# ElekShemaRelais.net
KiCad netlist of a schematic drawn in Altium Designer
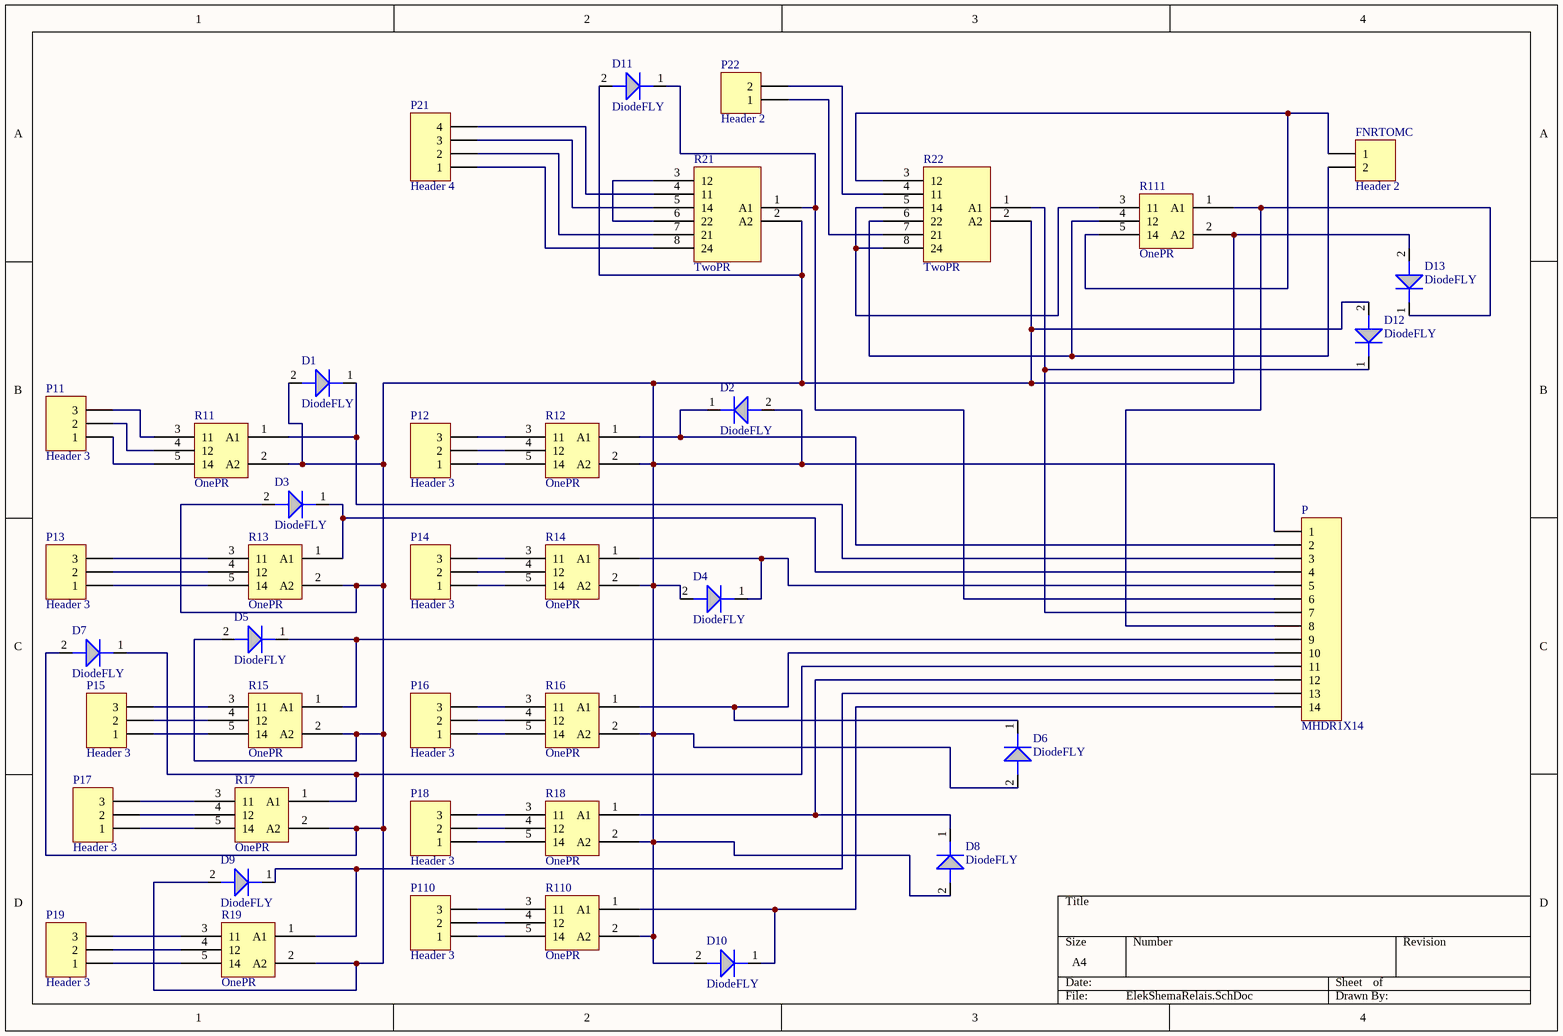
[diagram p0: ElekShemaRelais.SchDoc]

(export (version "E")
  (design (tool "Eeschema 10.0.6"))
  (components
    (comp (ref "D1") (value "DiodeFLY") (footprint "DiodeFLY") (libsource (lib "Schlib1") (part "DiodeFLY")))
    (comp (ref "D2") (value "DiodeFLY") (footprint "DiodeFLY") (libsource (lib "Schlib1") (part "DiodeFLY")))
    (comp (ref "D3") (value "DiodeFLY") (footprint "DiodeFLY") (libsource (lib "Schlib1") (part "DiodeFLY")))
    (comp (ref "D4") (value "DiodeFLY") (footprint "DiodeFLY") (libsource (lib "Schlib1") (part "DiodeFLY")))
    (comp (ref "D5") (value "DiodeFLY") (footprint "DiodeFLY") (libsource (lib "Schlib1") (part "DiodeFLY")))
    (comp (ref "D6") (value "DiodeFLY") (footprint "DiodeFLY") (libsource (lib "Schlib1") (part "DiodeFLY")))
    (comp (ref "D7") (value "DiodeFLY") (footprint "DiodeFLY") (libsource (lib "Schlib1") (part "DiodeFLY")))
    (comp (ref "D8") (value "DiodeFLY") (footprint "DiodeFLY") (libsource (lib "Schlib1") (part "DiodeFLY")))
    (comp (ref "D9") (value "DiodeFLY") (footprint "DiodeFLY") (libsource (lib "Schlib1") (part "DiodeFLY")))
    (comp (ref "D10") (value "DiodeFLY") (footprint "DiodeFLY") (libsource (lib "Schlib1") (part "DiodeFLY")))
    (comp (ref "D11") (value "DiodeFLY") (footprint "DiodeFLY") (libsource (lib "Schlib1") (part "DiodeFLY")))
    (comp (ref "D12") (value "DiodeFLY") (footprint "DiodeFLY") (libsource (lib "Schlib1") (part "DiodeFLY")))
    (comp (ref "D13") (value "DiodeFLY") (footprint "DiodeFLY") (libsource (lib "Schlib1") (part "DiodeFLY")))
    (comp (ref "FNRTOMC")
      (value "Header 2")
      (footprint "HDR2")
      (description "Header, 2-Pin")
      (fields (field (name "PUBLISHER") "Altium Limited"))
      (libsource (lib "") (part "Header 2_1"))
    )
    (comp (ref "P")
      (value "MHDR1X14")
      (footprint "HDR14")
      (description "Header, 14-Pin")
      (fields (field (name "PUBLISHER") "Altium Limited"))
      (libsource (lib "Miscellaneous Connectors") (part "MHDR1X14"))
    )
    (comp (ref "P11")
      (value "Header 3")
      (footprint "HDR3")
      (description "Header, 3-Pin")
      (fields (field (name "PUBLISHER") "Altium Limited"))
      (libsource (lib "Miscellaneous Connectors") (part "Header 3"))
    )
    (comp (ref "P12")
      (value "Header 3")
      (footprint "HDR3")
      (description "Header, 3-Pin")
      (fields (field (name "PUBLISHER") "Altium Limited"))
      (libsource (lib "Miscellaneous Connectors") (part "Header 3"))
    )
    (comp (ref "P13")
      (value "Header 3")
      (footprint "HDR3")
      (description "Header, 3-Pin")
      (fields (field (name "PUBLISHER") "Altium Limited"))
      (libsource (lib "Miscellaneous Connectors") (part "Header 3"))
    )
    (comp (ref "P14")
      (value "Header 3")
      (footprint "HDR3")
      (description "Header, 3-Pin")
      (fields (field (name "PUBLISHER") "Altium Limited"))
      (libsource (lib "Miscellaneous Connectors") (part "Header 3"))
    )
    (comp (ref "P15")
      (value "Header 3")
      (footprint "HDR3")
      (description "Header, 3-Pin")
      (fields (field (name "PUBLISHER") "Altium Limited"))
      (libsource (lib "Miscellaneous Connectors") (part "Header 3"))
    )
    (comp (ref "P16")
      (value "Header 3")
      (footprint "HDR3")
      (description "Header, 3-Pin")
      (fields (field (name "PUBLISHER") "Altium Limited"))
      (libsource (lib "Miscellaneous Connectors") (part "Header 3"))
    )
    (comp (ref "P17")
      (value "Header 3")
      (footprint "HDR3")
      (description "Header, 3-Pin")
      (fields (field (name "PUBLISHER") "Altium Limited"))
      (libsource (lib "Miscellaneous Connectors") (part "Header 3"))
    )
    (comp (ref "P18")
      (value "Header 3")
      (footprint "HDR3")
      (description "Header, 3-Pin")
      (fields (field (name "PUBLISHER") "Altium Limited"))
      (libsource (lib "Miscellaneous Connectors") (part "Header 3"))
    )
    (comp (ref "P19")
      (value "Header 3")
      (footprint "HDR3")
      (description "Header, 3-Pin")
      (fields (field (name "PUBLISHER") "Altium Limited"))
      (libsource (lib "Miscellaneous Connectors") (part "Header 3"))
    )
    (comp (ref "P21")
      (value "Header 4")
      (footprint "HDR4")
      (description "Header, 4-Pin")
      (fields (field (name "PUBLISHER") "Altium Limited"))
      (libsource (lib "Miscellaneous Connectors") (part "Header 4"))
    )
    (comp (ref "P22")
      (value "Header 2")
      (footprint "HDR2")
      (description "Header, 2-Pin")
      (fields (field (name "PUBLISHER") "Altium Limited"))
      (libsource (lib "Miscellaneous Connectors") (part "Header 2"))
    )
    (comp (ref "P110")
      (value "Header 3")
      (footprint "HDR3")
      (description "Header, 3-Pin")
      (fields (field (name "PUBLISHER") "Altium Limited"))
      (libsource (lib "Miscellaneous Connectors") (part "Header 3"))
    )
    (comp (ref "R11") (value "OnePR") (footprint "EENPOOL") (libsource (lib "Schlib1") (part "R1")))
    (comp (ref "R12") (value "OnePR") (footprint "EENPOOL") (libsource (lib "Schlib1") (part "R1")))
    (comp (ref "R13") (value "OnePR") (footprint "EENPOOL") (libsource (lib "Schlib1") (part "R1")))
    (comp (ref "R14") (value "OnePR") (footprint "EENPOOL") (libsource (lib "Schlib1") (part "R1")))
    (comp (ref "R15") (value "OnePR") (footprint "EENPOOL") (libsource (lib "Schlib1") (part "R1")))
    (comp (ref "R16") (value "OnePR") (footprint "EENPOOL") (libsource (lib "Schlib1") (part "R1")))
    (comp (ref "R17") (value "OnePR") (footprint "EENPOOL") (libsource (lib "Schlib1") (part "R1")))
    (comp (ref "R18") (value "OnePR") (footprint "EENPOOL") (libsource (lib "Schlib1") (part "R1")))
    (comp (ref "R19") (value "OnePR") (footprint "EENPOOL") (libsource (lib "Schlib1") (part "R1")))
    (comp (ref "R21") (value "TwoPR") (footprint "TWEEPOOL") (libsource (lib "Schlib1") (part "R2")))
    (comp (ref "R22") (value "TwoPR") (footprint "TWEEPOOL") (libsource (lib "Schlib1") (part "R2")))
    (comp (ref "R110") (value "OnePR") (footprint "EENPOOL") (libsource (lib "Schlib1") (part "R1")))
    (comp (ref "R111") (value "OnePR") (footprint "EENPOOL") (libsource (lib "Schlib1") (part "R1")))
  )
  (nets
    (net (code "1") (name "Net-(R11-11)") (class "Default")
      (node (ref "P11") (pin "3") (pinfunction "3_3") (pintype "passive"))
      (node (ref "R11") (pin "3") (pinfunction "11_3") (pintype "passive"))
    )
    (net (code "2") (name "Net-(R11-12)") (class "Default")
      (node (ref "P11") (pin "2") (pinfunction "2_2") (pintype "passive"))
      (node (ref "R11") (pin "4") (pinfunction "12_4") (pintype "passive"))
    )
    (net (code "3") (name "Net-(R11-14)") (class "Default")
      (node (ref "P11") (pin "1") (pinfunction "1_1") (pintype "passive"))
      (node (ref "R11") (pin "5") (pinfunction "14_5") (pintype "passive"))
    )
    (net (code "4") (name "Net-(R11-A1)") (class "Default")
      (node (ref "D1") (pin "1") (pintype "passive"))
      (node (ref "P") (pin "3") (pinfunction "3_3") (pintype "passive"))
      (node (ref "R11") (pin "1") (pinfunction "A1_1") (pintype "passive"))
    )
    (net (code "5") (name "Net-(R11-A2)") (class "Default")
      (node (ref "D1") (pin "2") (pintype "passive"))
      (node (ref "D10") (pin "2") (pintype "passive"))
      (node (ref "D11") (pin "2") (pintype "passive"))
      (node (ref "D12") (pin "2") (pintype "passive"))
      (node (ref "D13") (pin "2") (pintype "passive"))
      (node (ref "D2") (pin "2") (pintype "passive"))
      (node (ref "D3") (pin "2") (pintype "passive"))
      (node (ref "D4") (pin "2") (pintype "passive"))
      (node (ref "D5") (pin "2") (pintype "passive"))
      (node (ref "D6") (pin "2") (pintype "passive"))
      (node (ref "D7") (pin "2") (pintype "passive"))
      (node (ref "D8") (pin "2") (pintype "passive"))
      (node (ref "D9") (pin "2") (pintype "passive"))
      (node (ref "P") (pin "1") (pinfunction "1_1") (pintype "passive"))
      (node (ref "R11") (pin "2") (pinfunction "A2_2") (pintype "passive"))
      (node (ref "R110") (pin "2") (pinfunction "A2_2") (pintype "passive"))
      (node (ref "R111") (pin "2") (pinfunction "A2_2") (pintype "passive"))
      (node (ref "R12") (pin "2") (pinfunction "A2_2") (pintype "passive"))
      (node (ref "R13") (pin "2") (pinfunction "A2_2") (pintype "passive"))
      (node (ref "R14") (pin "2") (pinfunction "A2_2") (pintype "passive"))
      (node (ref "R15") (pin "2") (pinfunction "A2_2") (pintype "passive"))
      (node (ref "R16") (pin "2") (pinfunction "A2_2") (pintype "passive"))
      (node (ref "R17") (pin "2") (pinfunction "A2_2") (pintype "passive"))
      (node (ref "R18") (pin "2") (pinfunction "A2_2") (pintype "passive"))
      (node (ref "R19") (pin "2") (pinfunction "A2_2") (pintype "passive"))
      (node (ref "R21") (pin "2") (pinfunction "A2_2") (pintype "passive"))
      (node (ref "R22") (pin "2") (pinfunction "A2_2") (pintype "passive"))
    )
    (net (code "6") (name "Net-(R12-11)") (class "Default")
      (node (ref "P12") (pin "3") (pinfunction "3_3") (pintype "passive"))
      (node (ref "R12") (pin "3") (pinfunction "11_3") (pintype "passive"))
    )
    (net (code "7") (name "Net-(R12-12)") (class "Default")
      (node (ref "P12") (pin "2") (pinfunction "2_2") (pintype "passive"))
      (node (ref "R12") (pin "4") (pinfunction "12_4") (pintype "passive"))
    )
    (net (code "8") (name "Net-(R12-14)") (class "Default")
      (node (ref "P12") (pin "1") (pinfunction "1_1") (pintype "passive"))
      (node (ref "R12") (pin "5") (pinfunction "14_5") (pintype "passive"))
    )
    (net (code "9") (name "Net-(R12-A1)") (class "Default")
      (node (ref "D2") (pin "1") (pintype "passive"))
      (node (ref "P") (pin "2") (pinfunction "2_2") (pintype "passive"))
      (node (ref "R12") (pin "1") (pinfunction "A1_1") (pintype "passive"))
    )
    (net (code "10") (name "Net-(R13-11)") (class "Default")
      (node (ref "P13") (pin "3") (pinfunction "3_3") (pintype "passive"))
      (node (ref "R13") (pin "3") (pinfunction "11_3") (pintype "passive"))
    )
    (net (code "11") (name "Net-(R13-12)") (class "Default")
      (node (ref "P13") (pin "2") (pinfunction "2_2") (pintype "passive"))
      (node (ref "R13") (pin "4") (pinfunction "12_4") (pintype "passive"))
    )
    (net (code "12") (name "Net-(R13-14)") (class "Default")
      (node (ref "P13") (pin "1") (pinfunction "1_1") (pintype "passive"))
      (node (ref "R13") (pin "5") (pinfunction "14_5") (pintype "passive"))
    )
    (net (code "13") (name "Net-(R13-A1)") (class "Default")
      (node (ref "D3") (pin "1") (pintype "passive"))
      (node (ref "P") (pin "4") (pinfunction "4_4") (pintype "passive"))
      (node (ref "R13") (pin "1") (pinfunction "A1_1") (pintype "passive"))
    )
    (net (code "14") (name "Net-(R14-11)") (class "Default")
      (node (ref "P14") (pin "3") (pinfunction "3_3") (pintype "passive"))
      (node (ref "R14") (pin "3") (pinfunction "11_3") (pintype "passive"))
    )
    (net (code "15") (name "Net-(R14-12)") (class "Default")
      (node (ref "P14") (pin "2") (pinfunction "2_2") (pintype "passive"))
      (node (ref "R14") (pin "4") (pinfunction "12_4") (pintype "passive"))
    )
    (net (code "16") (name "Net-(R14-14)") (class "Default")
      (node (ref "P14") (pin "1") (pinfunction "1_1") (pintype "passive"))
      (node (ref "R14") (pin "5") (pinfunction "14_5") (pintype "passive"))
    )
    (net (code "17") (name "Net-(R14-A1)") (class "Default")
      (node (ref "D4") (pin "1") (pintype "passive"))
      (node (ref "P") (pin "5") (pinfunction "5_5") (pintype "passive"))
      (node (ref "R14") (pin "1") (pinfunction "A1_1") (pintype "passive"))
    )
    (net (code "18") (name "Net-(R15-11)") (class "Default")
      (node (ref "P15") (pin "3") (pinfunction "3_3") (pintype "passive"))
      (node (ref "R15") (pin "3") (pinfunction "11_3") (pintype "passive"))
    )
    (net (code "19") (name "Net-(R15-12)") (class "Default")
      (node (ref "P15") (pin "2") (pinfunction "2_2") (pintype "passive"))
      (node (ref "R15") (pin "4") (pinfunction "12_4") (pintype "passive"))
    )
    (net (code "20") (name "Net-(R15-14)") (class "Default")
      (node (ref "P15") (pin "1") (pinfunction "1_1") (pintype "passive"))
      (node (ref "R15") (pin "5") (pinfunction "14_5") (pintype "passive"))
    )
    (net (code "21") (name "Net-(R15-A1)") (class "Default")
      (node (ref "D5") (pin "1") (pintype "passive"))
      (node (ref "P") (pin "9") (pinfunction "9_9") (pintype "passive"))
      (node (ref "R15") (pin "1") (pinfunction "A1_1") (pintype "passive"))
    )
    (net (code "22") (name "Net-(R16-11)") (class "Default")
      (node (ref "P16") (pin "3") (pinfunction "3_3") (pintype "passive"))
      (node (ref "R16") (pin "3") (pinfunction "11_3") (pintype "passive"))
    )
    (net (code "23") (name "Net-(R16-12)") (class "Default")
      (node (ref "P16") (pin "2") (pinfunction "2_2") (pintype "passive"))
      (node (ref "R16") (pin "4") (pinfunction "12_4") (pintype "passive"))
    )
    (net (code "24") (name "Net-(R16-14)") (class "Default")
      (node (ref "P16") (pin "1") (pinfunction "1_1") (pintype "passive"))
      (node (ref "R16") (pin "5") (pinfunction "14_5") (pintype "passive"))
    )
    (net (code "25") (name "Net-(R16-A1)") (class "Default")
      (node (ref "D6") (pin "1") (pintype "passive"))
      (node (ref "P") (pin "10") (pinfunction "10_10") (pintype "passive"))
      (node (ref "R16") (pin "1") (pinfunction "A1_1") (pintype "passive"))
    )
    (net (code "26") (name "Net-(R17-11)") (class "Default")
      (node (ref "P17") (pin "3") (pinfunction "3_3") (pintype "passive"))
      (node (ref "R17") (pin "3") (pinfunction "11_3") (pintype "passive"))
    )
    (net (code "27") (name "Net-(R17-12)") (class "Default")
      (node (ref "P17") (pin "2") (pinfunction "2_2") (pintype "passive"))
      (node (ref "R17") (pin "4") (pinfunction "12_4") (pintype "passive"))
    )
    (net (code "28") (name "Net-(R17-14)") (class "Default")
      (node (ref "P17") (pin "1") (pinfunction "1_1") (pintype "passive"))
      (node (ref "R17") (pin "5") (pinfunction "14_5") (pintype "passive"))
    )
    (net (code "29") (name "Net-(R17-A1)") (class "Default")
      (node (ref "D7") (pin "1") (pintype "passive"))
      (node (ref "P") (pin "11") (pinfunction "11_11") (pintype "passive"))
      (node (ref "R17") (pin "1") (pinfunction "A1_1") (pintype "passive"))
    )
    (net (code "30") (name "Net-(R18-11)") (class "Default")
      (node (ref "P18") (pin "3") (pinfunction "3_3") (pintype "passive"))
      (node (ref "R18") (pin "3") (pinfunction "11_3") (pintype "passive"))
    )
    (net (code "31") (name "Net-(R18-12)") (class "Default")
      (node (ref "P18") (pin "2") (pinfunction "2_2") (pintype "passive"))
      (node (ref "R18") (pin "4") (pinfunction "12_4") (pintype "passive"))
    )
    (net (code "32") (name "Net-(R18-14)") (class "Default")
      (node (ref "P18") (pin "1") (pinfunction "1_1") (pintype "passive"))
      (node (ref "R18") (pin "5") (pinfunction "14_5") (pintype "passive"))
    )
    (net (code "33") (name "Net-(R18-A1)") (class "Default")
      (node (ref "D8") (pin "1") (pintype "passive"))
      (node (ref "P") (pin "12") (pinfunction "12_12") (pintype "passive"))
      (node (ref "R18") (pin "1") (pinfunction "A1_1") (pintype "passive"))
    )
    (net (code "34") (name "Net-(R19-11)") (class "Default")
      (node (ref "P19") (pin "3") (pinfunction "3_3") (pintype "passive"))
      (node (ref "R19") (pin "3") (pinfunction "11_3") (pintype "passive"))
    )
    (net (code "35") (name "Net-(R19-12)") (class "Default")
      (node (ref "P19") (pin "2") (pinfunction "2_2") (pintype "passive"))
      (node (ref "R19") (pin "4") (pinfunction "12_4") (pintype "passive"))
    )
    (net (code "36") (name "Net-(R19-14)") (class "Default")
      (node (ref "P19") (pin "1") (pinfunction "1_1") (pintype "passive"))
      (node (ref "R19") (pin "5") (pinfunction "14_5") (pintype "passive"))
    )
    (net (code "37") (name "Net-(R19-A1)") (class "Default")
      (node (ref "D9") (pin "1") (pintype "passive"))
      (node (ref "P") (pin "13") (pinfunction "13_13") (pintype "passive"))
      (node (ref "R19") (pin "1") (pinfunction "A1_1") (pintype "passive"))
    )
    (net (code "38") (name "Net-(R21-11)") (class "Default")
      (node (ref "P21") (pin "4") (pinfunction "4_4") (pintype "passive"))
      (node (ref "R21") (pin "4") (pinfunction "11_4") (pintype "passive"))
    )
    (net (code "39") (name "Net-(R21-12)") (class "Default")
      (node (ref "R21") (pin "3") (pinfunction "12_3") (pintype "passive"))
      (node (ref "R21") (pin "6") (pinfunction "22_6") (pintype "passive"))
    )
    (net (code "40") (name "Net-(R21-14)") (class "Default")
      (node (ref "P21") (pin "3") (pinfunction "3_3") (pintype "passive"))
      (node (ref "R21") (pin "5") (pinfunction "14_5") (pintype "passive"))
    )
    (net (code "41") (name "Net-(R21-21)") (class "Default")
      (node (ref "P21") (pin "2") (pinfunction "2_2") (pintype "passive"))
      (node (ref "R21") (pin "7") (pinfunction "21_7") (pintype "passive"))
    )
    (net (code "42") (name "Net-(R21-24)") (class "Default")
      (node (ref "P21") (pin "1") (pinfunction "1_1") (pintype "passive"))
      (node (ref "R21") (pin "8") (pinfunction "24_8") (pintype "passive"))
    )
    (net (code "43") (name "Net-(R21-A1)") (class "Default")
      (node (ref "D11") (pin "1") (pintype "passive"))
      (node (ref "P") (pin "6") (pinfunction "6_6") (pintype "passive"))
      (node (ref "R21") (pin "1") (pinfunction "A1_1") (pintype "passive"))
    )
    (net (code "44") (name "Net-(R22-11)") (class "Default")
      (node (ref "P22") (pin "2") (pinfunction "2_2") (pintype "passive"))
      (node (ref "R22") (pin "4") (pinfunction "11_4") (pintype "passive"))
    )
    (net (code "45") (name "Net-(R22-21)") (class "Default")
      (node (ref "P22") (pin "1") (pinfunction "1_1") (pintype "passive"))
      (node (ref "R22") (pin "7") (pinfunction "21_7") (pintype "passive"))
    )
    (net (code "46") (name "Net-(R22-A1)") (class "Default")
      (node (ref "D12") (pin "1") (pintype "passive"))
      (node (ref "P") (pin "7") (pinfunction "7_7") (pintype "passive"))
      (node (ref "R22") (pin "1") (pinfunction "A1_1") (pintype "passive"))
    )
    (net (code "47") (name "Net-(R110-11)") (class "Default")
      (node (ref "P110") (pin "3") (pinfunction "3_3") (pintype "passive"))
      (node (ref "R110") (pin "3") (pinfunction "11_3") (pintype "passive"))
    )
    (net (code "48") (name "Net-(R110-12)") (class "Default")
      (node (ref "P110") (pin "2") (pinfunction "2_2") (pintype "passive"))
      (node (ref "R110") (pin "4") (pinfunction "12_4") (pintype "passive"))
    )
    (net (code "49") (name "Net-(R110-14)") (class "Default")
      (node (ref "P110") (pin "1") (pinfunction "1_1") (pintype "passive"))
      (node (ref "R110") (pin "5") (pinfunction "14_5") (pintype "passive"))
    )
    (net (code "50") (name "Net-(R110-A1)") (class "Default")
      (node (ref "D10") (pin "1") (pintype "passive"))
      (node (ref "P") (pin "14") (pinfunction "14_14") (pintype "passive"))
      (node (ref "R110") (pin "1") (pinfunction "A1_1") (pintype "passive"))
    )
    (net (code "51") (name "Net-(R111-11)") (class "Default")
      (node (ref "R111") (pin "3") (pinfunction "11_3") (pintype "passive"))
      (node (ref "R22") (pin "5") (pinfunction "14_5") (pintype "passive"))
      (node (ref "R22") (pin "8") (pinfunction "24_8") (pintype "passive"))
    )
    (net (code "52") (name "Net-(R111-12)") (class "Default")
      (node (ref "FNRTOMC") (pin "2") (pinfunction "2_2") (pintype "passive"))
      (node (ref "R111") (pin "4") (pinfunction "12_4") (pintype "passive"))
      (node (ref "R22") (pin "6") (pinfunction "22_6") (pintype "passive"))
    )
    (net (code "53") (name "Net-(R111-14)") (class "Default")
      (node (ref "FNRTOMC") (pin "1") (pinfunction "1_1") (pintype "passive"))
      (node (ref "R111") (pin "5") (pinfunction "14_5") (pintype "passive"))
      (node (ref "R22") (pin "3") (pinfunction "12_3") (pintype "passive"))
    )
    (net (code "54") (name "Net-(R111-A1)") (class "Default")
      (node (ref "D13") (pin "1") (pintype "passive"))
      (node (ref "P") (pin "8") (pinfunction "8_8") (pintype "passive"))
      (node (ref "R111") (pin "1") (pinfunction "A1_1") (pintype "passive"))
    )
  )
)
